# working.net
KiCad netlist of a schematic drawn in EAGLE
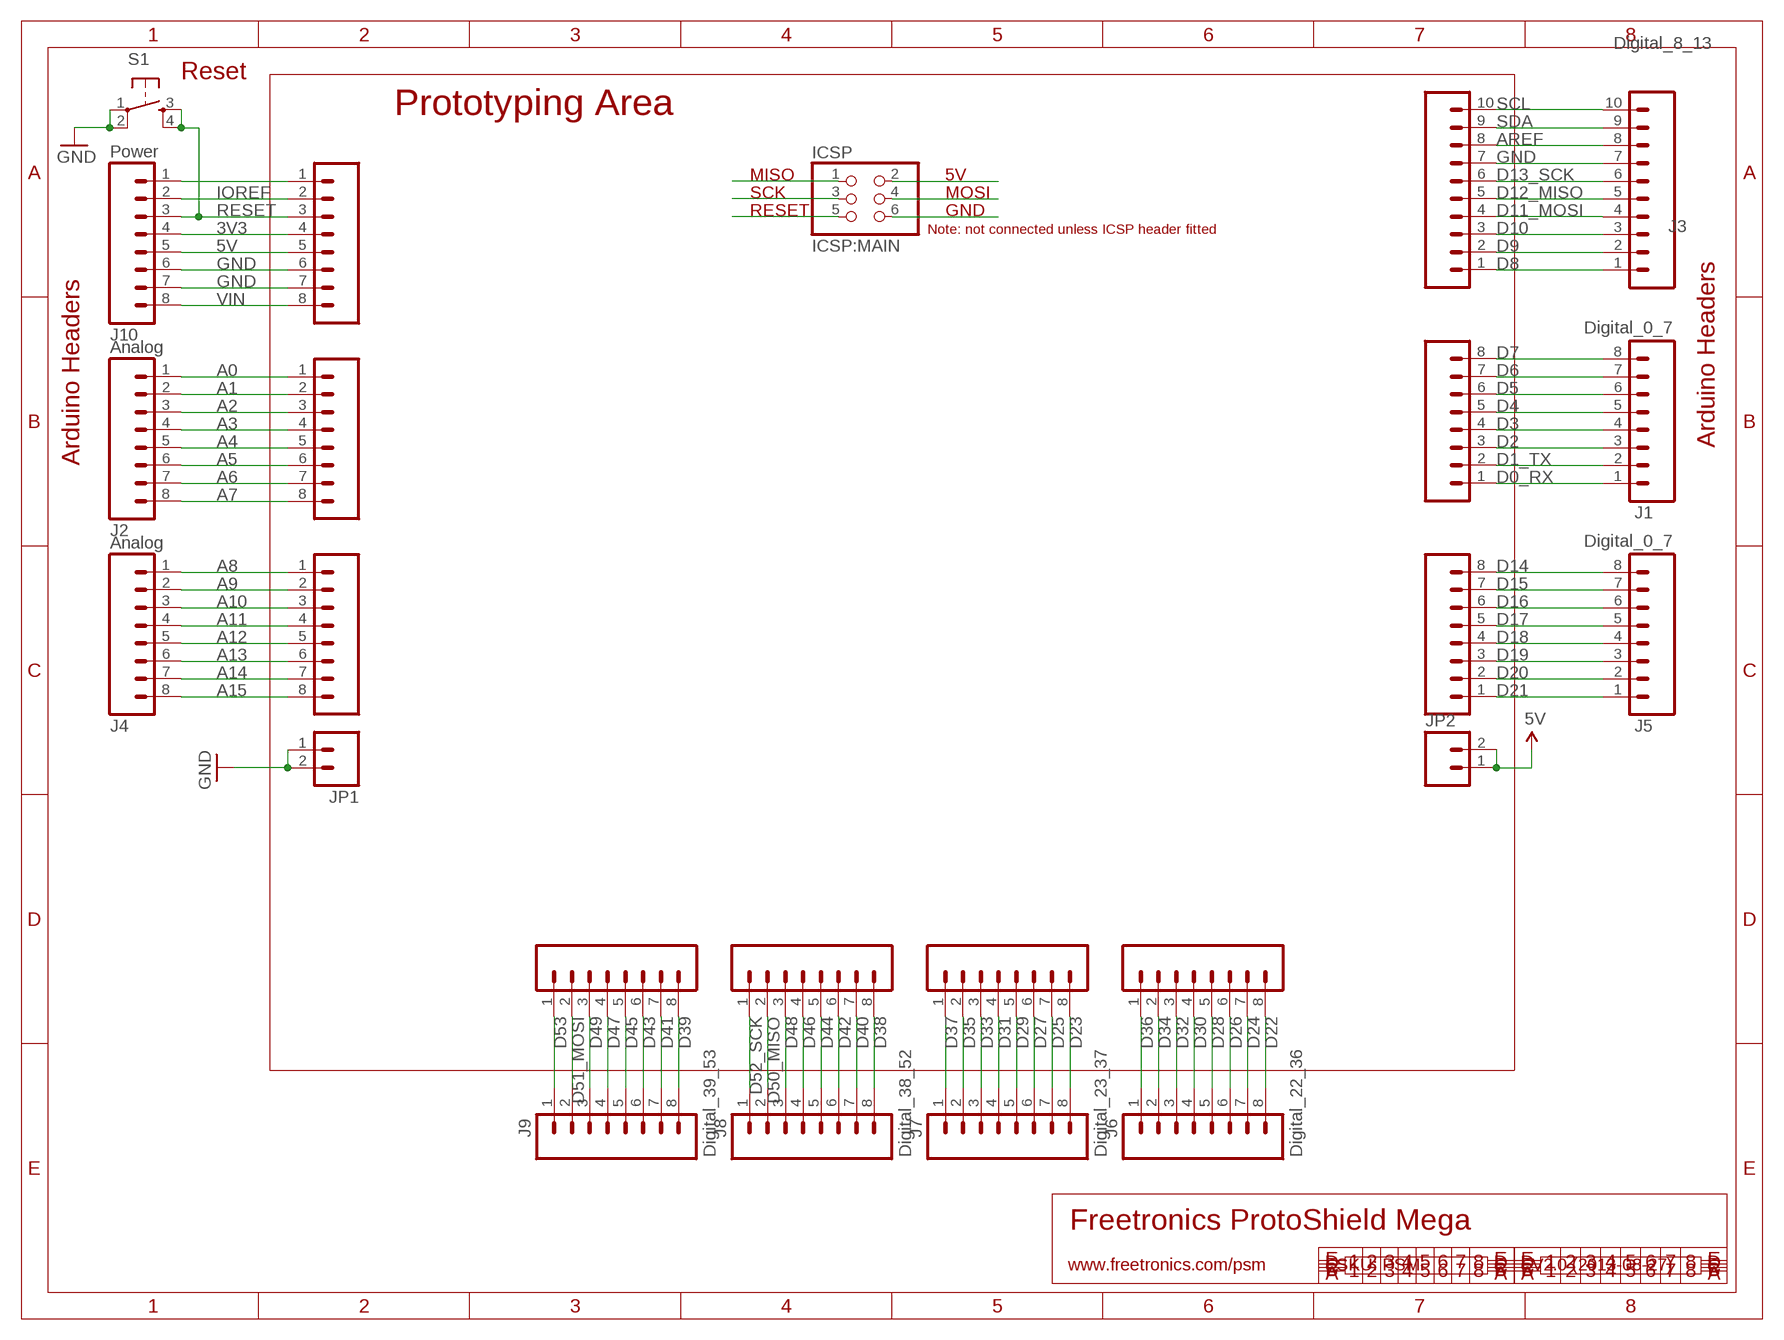
[diagram p0: schematic, sheet 1]

(export (version "E")
  (design (tool "Eeschema 10.0.6"))
  (components
    (comp (ref "ICSP")
      (value "ICSP:MAIN")
      (footprint "eagle-import:2X03")
      (libsource (lib "eagle-import") (part "PINHD-2X3"))
    )
    (comp (ref "J1")
      (value "Digital_0_7")
      (footprint "eagle-import:1X08")
      (libsource (lib "eagle-import") (part "M08"))
    )
    (comp (ref "J2")
      (value "Analog")
      (footprint "eagle-import:1X08")
      (libsource (lib "eagle-import") (part "freetronics-master-v1_M08"))
    )
    (comp (ref "J3")
      (value "Digital_8_13")
      (footprint "eagle-import:1X10")
      (libsource (lib "eagle-import") (part "M100.1"))
    )
    (comp (ref "J4")
      (value "Analog")
      (footprint "eagle-import:1X08")
      (libsource (lib "eagle-import") (part "freetronics-master-v1_M08"))
    )
    (comp (ref "J5")
      (value "Digital_0_7")
      (footprint "eagle-import:1X08")
      (libsource (lib "eagle-import") (part "M08"))
    )
    (comp (ref "J6")
      (value "Digital_22_36")
      (footprint "eagle-import:1X08")
      (libsource (lib "eagle-import") (part "M08"))
    )
    (comp (ref "J7")
      (value "Digital_23_37")
      (footprint "eagle-import:1X08")
      (libsource (lib "eagle-import") (part "M08"))
    )
    (comp (ref "J8")
      (value "Digital_38_52")
      (footprint "eagle-import:1X08")
      (libsource (lib "eagle-import") (part "M08"))
    )
    (comp (ref "J9")
      (value "Digital_39_53")
      (footprint "eagle-import:1X08")
      (libsource (lib "eagle-import") (part "M08"))
    )
    (comp (ref "J10")
      (value "Power")
      (footprint "eagle-import:1X08")
      (libsource (lib "eagle-import") (part "freetronics-master-v1_M08"))
    )
    (comp (ref "JP1")
      (value "M02PTH")
      (footprint "eagle-import:1X02")
      (libsource (lib "eagle-import") (part "M02PTH"))
    )
    (comp (ref "JP2")
      (value "M02PTH")
      (footprint "eagle-import:1X02")
      (libsource (lib "eagle-import") (part "M02PTH"))
    )
    (comp (ref "S1")
      (value "TAC_SWITCHPTH")
      (footprint "eagle-import:TACTILE-PTH")
      (libsource (lib "eagle-import") (part "TAC_SWITCHPTH"))
    )
    (comp (ref "SL1")
      (value "Digital_0_7")
      (footprint "eagle-import:1X08")
      (libsource (lib "eagle-import") (part "M08"))
    )
    (comp (ref "SL2")
      (value "Analog")
      (footprint "eagle-import:1X08")
      (libsource (lib "eagle-import") (part "freetronics-master-v1_M08"))
    )
    (comp (ref "SL3")
      (value "Digital_8_13")
      (footprint "eagle-import:1X10")
      (libsource (lib "eagle-import") (part "M100.1"))
    )
    (comp (ref "SL4")
      (value "Analog")
      (footprint "eagle-import:1X08")
      (libsource (lib "eagle-import") (part "freetronics-master-v1_M08"))
    )
    (comp (ref "SL5")
      (value "Digital_0_7")
      (footprint "eagle-import:1X08")
      (libsource (lib "eagle-import") (part "M08"))
    )
    (comp (ref "SL6")
      (value "Digital_0_7")
      (footprint "eagle-import:1X08")
      (libsource (lib "eagle-import") (part "M08"))
    )
    (comp (ref "SL7")
      (value "Digital_0_7")
      (footprint "eagle-import:1X08")
      (libsource (lib "eagle-import") (part "M08"))
    )
    (comp (ref "SL8")
      (value "Digital_0_7")
      (footprint "eagle-import:1X08")
      (libsource (lib "eagle-import") (part "M08"))
    )
    (comp (ref "SL9")
      (value "Digital_0_7")
      (footprint "eagle-import:1X08")
      (libsource (lib "eagle-import") (part "M08"))
    )
    (comp (ref "SLP")
      (value "Power")
      (footprint "eagle-import:1X08")
      (libsource (lib "eagle-import") (part "freetronics-master-v1_M08"))
    )
  )
  (nets
    (net (code "1") (name "/3V3") (class "Default")
      (node (ref "J10") (pin "4") (pinfunction "4_4") (pintype "passive"))
      (node (ref "SLP") (pin "4") (pinfunction "4_4") (pintype "passive"))
    )
    (net (code "2") (name "/A0") (class "Default")
      (node (ref "J2") (pin "1") (pinfunction "1_1") (pintype "passive"))
      (node (ref "SL2") (pin "1") (pinfunction "1_1") (pintype "passive"))
    )
    (net (code "3") (name "/A1") (class "Default")
      (node (ref "J2") (pin "2") (pinfunction "2_2") (pintype "passive"))
      (node (ref "SL2") (pin "2") (pinfunction "2_2") (pintype "passive"))
    )
    (net (code "4") (name "/A2") (class "Default")
      (node (ref "J2") (pin "3") (pinfunction "3_3") (pintype "passive"))
      (node (ref "SL2") (pin "3") (pinfunction "3_3") (pintype "passive"))
    )
    (net (code "5") (name "/A3") (class "Default")
      (node (ref "J2") (pin "4") (pinfunction "4_4") (pintype "passive"))
      (node (ref "SL2") (pin "4") (pinfunction "4_4") (pintype "passive"))
    )
    (net (code "6") (name "/A4") (class "Default")
      (node (ref "J2") (pin "5") (pinfunction "5_5") (pintype "passive"))
      (node (ref "SL2") (pin "5") (pinfunction "5_5") (pintype "passive"))
    )
    (net (code "7") (name "/A5") (class "Default")
      (node (ref "J2") (pin "6") (pinfunction "6_6") (pintype "passive"))
      (node (ref "SL2") (pin "6") (pinfunction "6_6") (pintype "passive"))
    )
    (net (code "8") (name "/A6") (class "Default")
      (node (ref "J2") (pin "7") (pinfunction "7_7") (pintype "passive"))
      (node (ref "SL2") (pin "7") (pinfunction "7_7") (pintype "passive"))
    )
    (net (code "9") (name "/A7") (class "Default")
      (node (ref "J2") (pin "8") (pinfunction "8_8") (pintype "passive"))
      (node (ref "SL2") (pin "8") (pinfunction "8_8") (pintype "passive"))
    )
    (net (code "10") (name "/A8") (class "Default")
      (node (ref "J4") (pin "1") (pinfunction "1_1") (pintype "passive"))
      (node (ref "SL4") (pin "1") (pinfunction "1_1") (pintype "passive"))
    )
    (net (code "11") (name "/A9") (class "Default")
      (node (ref "J4") (pin "2") (pinfunction "2_2") (pintype "passive"))
      (node (ref "SL4") (pin "2") (pinfunction "2_2") (pintype "passive"))
    )
    (net (code "12") (name "/A10") (class "Default")
      (node (ref "J4") (pin "3") (pinfunction "3_3") (pintype "passive"))
      (node (ref "SL4") (pin "3") (pinfunction "3_3") (pintype "passive"))
    )
    (net (code "13") (name "/A11") (class "Default")
      (node (ref "J4") (pin "4") (pinfunction "4_4") (pintype "passive"))
      (node (ref "SL4") (pin "4") (pinfunction "4_4") (pintype "passive"))
    )
    (net (code "14") (name "/A12") (class "Default")
      (node (ref "J4") (pin "5") (pinfunction "5_5") (pintype "passive"))
      (node (ref "SL4") (pin "5") (pinfunction "5_5") (pintype "passive"))
    )
    (net (code "15") (name "/A13") (class "Default")
      (node (ref "J4") (pin "6") (pinfunction "6_6") (pintype "passive"))
      (node (ref "SL4") (pin "6") (pinfunction "6_6") (pintype "passive"))
    )
    (net (code "16") (name "/A14") (class "Default")
      (node (ref "J4") (pin "7") (pinfunction "7_7") (pintype "passive"))
      (node (ref "SL4") (pin "7") (pinfunction "7_7") (pintype "passive"))
    )
    (net (code "17") (name "/A15") (class "Default")
      (node (ref "J4") (pin "8") (pinfunction "8_8") (pintype "passive"))
      (node (ref "SL4") (pin "8") (pinfunction "8_8") (pintype "passive"))
    )
    (net (code "18") (name "/AREF") (class "Default")
      (node (ref "J3") (pin "8") (pinfunction "8_8") (pintype "passive"))
      (node (ref "SL3") (pin "8") (pinfunction "8_8") (pintype "passive"))
    )
    (net (code "19") (name "/D0_RX") (class "Default")
      (node (ref "J1") (pin "1") (pinfunction "1_1") (pintype "passive"))
      (node (ref "SL1") (pin "1") (pinfunction "1_1") (pintype "passive"))
    )
    (net (code "20") (name "/D1_TX") (class "Default")
      (node (ref "J1") (pin "2") (pinfunction "2_2") (pintype "passive"))
      (node (ref "SL1") (pin "2") (pinfunction "2_2") (pintype "passive"))
    )
    (net (code "21") (name "/D2") (class "Default")
      (node (ref "J1") (pin "3") (pinfunction "3_3") (pintype "passive"))
      (node (ref "SL1") (pin "3") (pinfunction "3_3") (pintype "passive"))
    )
    (net (code "22") (name "/D3") (class "Default")
      (node (ref "J1") (pin "4") (pinfunction "4_4") (pintype "passive"))
      (node (ref "SL1") (pin "4") (pinfunction "4_4") (pintype "passive"))
    )
    (net (code "23") (name "/D4") (class "Default")
      (node (ref "J1") (pin "5") (pinfunction "5_5") (pintype "passive"))
      (node (ref "SL1") (pin "5") (pinfunction "5_5") (pintype "passive"))
    )
    (net (code "24") (name "/D5") (class "Default")
      (node (ref "J1") (pin "6") (pinfunction "6_6") (pintype "passive"))
      (node (ref "SL1") (pin "6") (pinfunction "6_6") (pintype "passive"))
    )
    (net (code "25") (name "/D6") (class "Default")
      (node (ref "J1") (pin "7") (pinfunction "7_7") (pintype "passive"))
      (node (ref "SL1") (pin "7") (pinfunction "7_7") (pintype "passive"))
    )
    (net (code "26") (name "/D7") (class "Default")
      (node (ref "J1") (pin "8") (pinfunction "8_8") (pintype "passive"))
      (node (ref "SL1") (pin "8") (pinfunction "8_8") (pintype "passive"))
    )
    (net (code "27") (name "/D8") (class "Default")
      (node (ref "J3") (pin "1") (pinfunction "1_1") (pintype "passive"))
      (node (ref "SL3") (pin "1") (pinfunction "1_1") (pintype "passive"))
    )
    (net (code "28") (name "/D9") (class "Default")
      (node (ref "J3") (pin "2") (pinfunction "2_2") (pintype "passive"))
      (node (ref "SL3") (pin "2") (pinfunction "2_2") (pintype "passive"))
    )
    (net (code "29") (name "/D10") (class "Default")
      (node (ref "J3") (pin "3") (pinfunction "3_3") (pintype "passive"))
      (node (ref "SL3") (pin "3") (pinfunction "3_3") (pintype "passive"))
    )
    (net (code "30") (name "/D11_MOSI") (class "Default")
      (node (ref "J3") (pin "4") (pinfunction "4_4") (pintype "passive"))
      (node (ref "SL3") (pin "4") (pinfunction "4_4") (pintype "passive"))
    )
    (net (code "31") (name "/D12_MISO") (class "Default")
      (node (ref "J3") (pin "5") (pinfunction "5_5") (pintype "passive"))
      (node (ref "SL3") (pin "5") (pinfunction "5_5") (pintype "passive"))
    )
    (net (code "32") (name "/D13_SCK") (class "Default")
      (node (ref "J3") (pin "6") (pinfunction "6_6") (pintype "passive"))
      (node (ref "SL3") (pin "6") (pinfunction "6_6") (pintype "passive"))
    )
    (net (code "33") (name "/D14") (class "Default")
      (node (ref "J5") (pin "8") (pinfunction "8_8") (pintype "passive"))
      (node (ref "SL5") (pin "8") (pinfunction "8_8") (pintype "passive"))
    )
    (net (code "34") (name "/D15") (class "Default")
      (node (ref "J5") (pin "7") (pinfunction "7_7") (pintype "passive"))
      (node (ref "SL5") (pin "7") (pinfunction "7_7") (pintype "passive"))
    )
    (net (code "35") (name "/D16") (class "Default")
      (node (ref "J5") (pin "6") (pinfunction "6_6") (pintype "passive"))
      (node (ref "SL5") (pin "6") (pinfunction "6_6") (pintype "passive"))
    )
    (net (code "36") (name "/D17") (class "Default")
      (node (ref "J5") (pin "5") (pinfunction "5_5") (pintype "passive"))
      (node (ref "SL5") (pin "5") (pinfunction "5_5") (pintype "passive"))
    )
    (net (code "37") (name "/D18") (class "Default")
      (node (ref "J5") (pin "4") (pinfunction "4_4") (pintype "passive"))
      (node (ref "SL5") (pin "4") (pinfunction "4_4") (pintype "passive"))
    )
    (net (code "38") (name "/D19") (class "Default")
      (node (ref "J5") (pin "3") (pinfunction "3_3") (pintype "passive"))
      (node (ref "SL5") (pin "3") (pinfunction "3_3") (pintype "passive"))
    )
    (net (code "39") (name "/D20") (class "Default")
      (node (ref "J5") (pin "2") (pinfunction "2_2") (pintype "passive"))
      (node (ref "SL5") (pin "2") (pinfunction "2_2") (pintype "passive"))
    )
    (net (code "40") (name "/D21") (class "Default")
      (node (ref "J5") (pin "1") (pinfunction "1_1") (pintype "passive"))
      (node (ref "SL5") (pin "1") (pinfunction "1_1") (pintype "passive"))
    )
    (net (code "41") (name "/D22") (class "Default")
      (node (ref "J6") (pin "8") (pinfunction "8_8") (pintype "passive"))
      (node (ref "SL6") (pin "8") (pinfunction "8_8") (pintype "passive"))
    )
    (net (code "42") (name "/D23") (class "Default")
      (node (ref "J7") (pin "8") (pinfunction "8_8") (pintype "passive"))
      (node (ref "SL7") (pin "8") (pinfunction "8_8") (pintype "passive"))
    )
    (net (code "43") (name "/D24") (class "Default")
      (node (ref "J6") (pin "7") (pinfunction "7_7") (pintype "passive"))
      (node (ref "SL6") (pin "7") (pinfunction "7_7") (pintype "passive"))
    )
    (net (code "44") (name "/D25") (class "Default")
      (node (ref "J7") (pin "7") (pinfunction "7_7") (pintype "passive"))
      (node (ref "SL7") (pin "7") (pinfunction "7_7") (pintype "passive"))
    )
    (net (code "45") (name "/D26") (class "Default")
      (node (ref "J6") (pin "6") (pinfunction "6_6") (pintype "passive"))
      (node (ref "SL6") (pin "6") (pinfunction "6_6") (pintype "passive"))
    )
    (net (code "46") (name "/D27") (class "Default")
      (node (ref "J7") (pin "6") (pinfunction "6_6") (pintype "passive"))
      (node (ref "SL7") (pin "6") (pinfunction "6_6") (pintype "passive"))
    )
    (net (code "47") (name "/D28") (class "Default")
      (node (ref "J6") (pin "5") (pinfunction "5_5") (pintype "passive"))
      (node (ref "SL6") (pin "5") (pinfunction "5_5") (pintype "passive"))
    )
    (net (code "48") (name "/D29") (class "Default")
      (node (ref "J7") (pin "5") (pinfunction "5_5") (pintype "passive"))
      (node (ref "SL7") (pin "5") (pinfunction "5_5") (pintype "passive"))
    )
    (net (code "49") (name "/D30") (class "Default")
      (node (ref "J6") (pin "4") (pinfunction "4_4") (pintype "passive"))
      (node (ref "SL6") (pin "4") (pinfunction "4_4") (pintype "passive"))
    )
    (net (code "50") (name "/D31") (class "Default")
      (node (ref "J7") (pin "4") (pinfunction "4_4") (pintype "passive"))
      (node (ref "SL7") (pin "4") (pinfunction "4_4") (pintype "passive"))
    )
    (net (code "51") (name "/D32") (class "Default")
      (node (ref "J6") (pin "3") (pinfunction "3_3") (pintype "passive"))
      (node (ref "SL6") (pin "3") (pinfunction "3_3") (pintype "passive"))
    )
    (net (code "52") (name "/D33") (class "Default")
      (node (ref "J7") (pin "3") (pinfunction "3_3") (pintype "passive"))
      (node (ref "SL7") (pin "3") (pinfunction "3_3") (pintype "passive"))
    )
    (net (code "53") (name "/D34") (class "Default")
      (node (ref "J6") (pin "2") (pinfunction "2_2") (pintype "passive"))
      (node (ref "SL6") (pin "2") (pinfunction "2_2") (pintype "passive"))
    )
    (net (code "54") (name "/D35") (class "Default")
      (node (ref "J7") (pin "2") (pinfunction "2_2") (pintype "passive"))
      (node (ref "SL7") (pin "2") (pinfunction "2_2") (pintype "passive"))
    )
    (net (code "55") (name "/D36") (class "Default")
      (node (ref "J6") (pin "1") (pinfunction "1_1") (pintype "passive"))
      (node (ref "SL6") (pin "1") (pinfunction "1_1") (pintype "passive"))
    )
    (net (code "56") (name "/D37") (class "Default")
      (node (ref "J7") (pin "1") (pinfunction "1_1") (pintype "passive"))
      (node (ref "SL7") (pin "1") (pinfunction "1_1") (pintype "passive"))
    )
    (net (code "57") (name "/D38") (class "Default")
      (node (ref "J8") (pin "8") (pinfunction "8_8") (pintype "passive"))
      (node (ref "SL8") (pin "8") (pinfunction "8_8") (pintype "passive"))
    )
    (net (code "58") (name "/D39") (class "Default")
      (node (ref "J9") (pin "8") (pinfunction "8_8") (pintype "passive"))
      (node (ref "SL9") (pin "8") (pinfunction "8_8") (pintype "passive"))
    )
    (net (code "59") (name "/D40") (class "Default")
      (node (ref "J8") (pin "7") (pinfunction "7_7") (pintype "passive"))
      (node (ref "SL8") (pin "7") (pinfunction "7_7") (pintype "passive"))
    )
    (net (code "60") (name "/D41") (class "Default")
      (node (ref "J9") (pin "7") (pinfunction "7_7") (pintype "passive"))
      (node (ref "SL9") (pin "7") (pinfunction "7_7") (pintype "passive"))
    )
    (net (code "61") (name "/D42") (class "Default")
      (node (ref "J8") (pin "6") (pinfunction "6_6") (pintype "passive"))
      (node (ref "SL8") (pin "6") (pinfunction "6_6") (pintype "passive"))
    )
    (net (code "62") (name "/D43") (class "Default")
      (node (ref "J9") (pin "6") (pinfunction "6_6") (pintype "passive"))
      (node (ref "SL9") (pin "6") (pinfunction "6_6") (pintype "passive"))
    )
    (net (code "63") (name "/D44") (class "Default")
      (node (ref "J8") (pin "5") (pinfunction "5_5") (pintype "passive"))
      (node (ref "SL8") (pin "5") (pinfunction "5_5") (pintype "passive"))
    )
    (net (code "64") (name "/D45") (class "Default")
      (node (ref "J9") (pin "5") (pinfunction "5_5") (pintype "passive"))
      (node (ref "SL9") (pin "5") (pinfunction "5_5") (pintype "passive"))
    )
    (net (code "65") (name "/D46") (class "Default")
      (node (ref "J8") (pin "4") (pinfunction "4_4") (pintype "passive"))
      (node (ref "SL8") (pin "4") (pinfunction "4_4") (pintype "passive"))
    )
    (net (code "66") (name "/D47") (class "Default")
      (node (ref "J9") (pin "4") (pinfunction "4_4") (pintype "passive"))
      (node (ref "SL9") (pin "4") (pinfunction "4_4") (pintype "passive"))
    )
    (net (code "67") (name "/D48") (class "Default")
      (node (ref "J8") (pin "3") (pinfunction "3_3") (pintype "passive"))
      (node (ref "SL8") (pin "3") (pinfunction "3_3") (pintype "passive"))
    )
    (net (code "68") (name "/D49") (class "Default")
      (node (ref "J9") (pin "3") (pinfunction "3_3") (pintype "passive"))
      (node (ref "SL9") (pin "3") (pinfunction "3_3") (pintype "passive"))
    )
    (net (code "69") (name "/D50_MISO") (class "Default")
      (node (ref "J8") (pin "2") (pinfunction "2_2") (pintype "passive"))
      (node (ref "SL8") (pin "2") (pinfunction "2_2") (pintype "passive"))
    )
    (net (code "70") (name "/D51_MOSI") (class "Default")
      (node (ref "J9") (pin "2") (pinfunction "2_2") (pintype "passive"))
      (node (ref "SL9") (pin "2") (pinfunction "2_2") (pintype "passive"))
    )
    (net (code "71") (name "/D52_SCK") (class "Default")
      (node (ref "J8") (pin "1") (pinfunction "1_1") (pintype "passive"))
      (node (ref "SL8") (pin "1") (pinfunction "1_1") (pintype "passive"))
    )
    (net (code "72") (name "/D53") (class "Default")
      (node (ref "J9") (pin "1") (pinfunction "1_1") (pintype "passive"))
      (node (ref "SL9") (pin "1") (pinfunction "1_1") (pintype "passive"))
    )
    (net (code "73") (name "/IOREF") (class "Default")
      (node (ref "J10") (pin "2") (pinfunction "2_2") (pintype "passive"))
      (node (ref "SLP") (pin "2") (pinfunction "2_2") (pintype "passive"))
    )
    (net (code "74") (name "/RESET") (class "Default")
      (node (ref "J10") (pin "3") (pinfunction "3_3") (pintype "passive"))
      (node (ref "S1") (pin "3") (pinfunction "3_3") (pintype "passive"))
      (node (ref "S1") (pin "4") (pinfunction "4_4") (pintype "passive"))
      (node (ref "SLP") (pin "3") (pinfunction "3_3") (pintype "passive"))
    )
    (net (code "75") (name "/SCL") (class "Default")
      (node (ref "J3") (pin "10") (pinfunction "10_10") (pintype "passive"))
      (node (ref "SL3") (pin "10") (pinfunction "10_10") (pintype "passive"))
    )
    (net (code "76") (name "/SDA") (class "Default")
      (node (ref "J3") (pin "9") (pinfunction "9_9") (pintype "passive"))
      (node (ref "SL3") (pin "9") (pinfunction "9_9") (pintype "passive"))
    )
    (net (code "77") (name "/VIN") (class "Default")
      (node (ref "J10") (pin "8") (pinfunction "8_8") (pintype "passive"))
      (node (ref "SLP") (pin "8") (pinfunction "8_8") (pintype "passive"))
    )
    (net (code "78") (name "5V") (class "Default")
      (node (ref "J10") (pin "5") (pinfunction "5_5") (pintype "passive"))
      (node (ref "JP2") (pin "1") (pinfunction "1_1") (pintype "passive"))
      (node (ref "JP2") (pin "2") (pinfunction "2_2") (pintype "passive"))
      (node (ref "SLP") (pin "5") (pinfunction "5_5") (pintype "passive"))
    )
    (net (code "79") (name "GND") (class "Default")
      (node (ref "J10") (pin "6") (pinfunction "6_6") (pintype "passive"))
      (node (ref "J10") (pin "7") (pinfunction "7_7") (pintype "passive"))
      (node (ref "J3") (pin "7") (pinfunction "7_7") (pintype "passive"))
      (node (ref "JP1") (pin "1") (pinfunction "1_1") (pintype "passive"))
      (node (ref "JP1") (pin "2") (pinfunction "2_2") (pintype "passive"))
      (node (ref "S1") (pin "1") (pinfunction "1_1") (pintype "passive"))
      (node (ref "S1") (pin "2") (pinfunction "2_2") (pintype "passive"))
      (node (ref "SL3") (pin "7") (pinfunction "7_7") (pintype "passive"))
      (node (ref "SLP") (pin "6") (pinfunction "6_6") (pintype "passive"))
      (node (ref "SLP") (pin "7") (pinfunction "7_7") (pintype "passive"))
    )
    (net (code "80") (name "Net-(J10-Pad1)") (class "Default")
      (node (ref "J10") (pin "1") (pinfunction "1_1") (pintype "passive"))
      (node (ref "SLP") (pin "1") (pinfunction "1_1") (pintype "passive"))
    )
    (net (code "81") (name "unconnected-(ICSP-Pad1)") (class "Default")
      (node (ref "ICSP") (pin "1") (pinfunction "1_1") (pintype "passive"))
    )
    (net (code "82") (name "unconnected-(ICSP-Pad2)") (class "Default")
      (node (ref "ICSP") (pin "2") (pinfunction "2_2") (pintype "passive"))
    )
    (net (code "83") (name "unconnected-(ICSP-Pad3)") (class "Default")
      (node (ref "ICSP") (pin "3") (pinfunction "3_3") (pintype "passive"))
    )
    (net (code "84") (name "unconnected-(ICSP-Pad4)") (class "Default")
      (node (ref "ICSP") (pin "4") (pinfunction "4_4") (pintype "passive"))
    )
    (net (code "85") (name "unconnected-(ICSP-Pad5)") (class "Default")
      (node (ref "ICSP") (pin "5") (pinfunction "5_5") (pintype "passive"))
    )
    (net (code "86") (name "unconnected-(ICSP-Pad6)") (class "Default")
      (node (ref "ICSP") (pin "6") (pinfunction "6_6") (pintype "passive"))
    )
  )
)
